# KAKUTE_mini.net
KiCad netlist of a schematic drawn in EasyEDA Pro
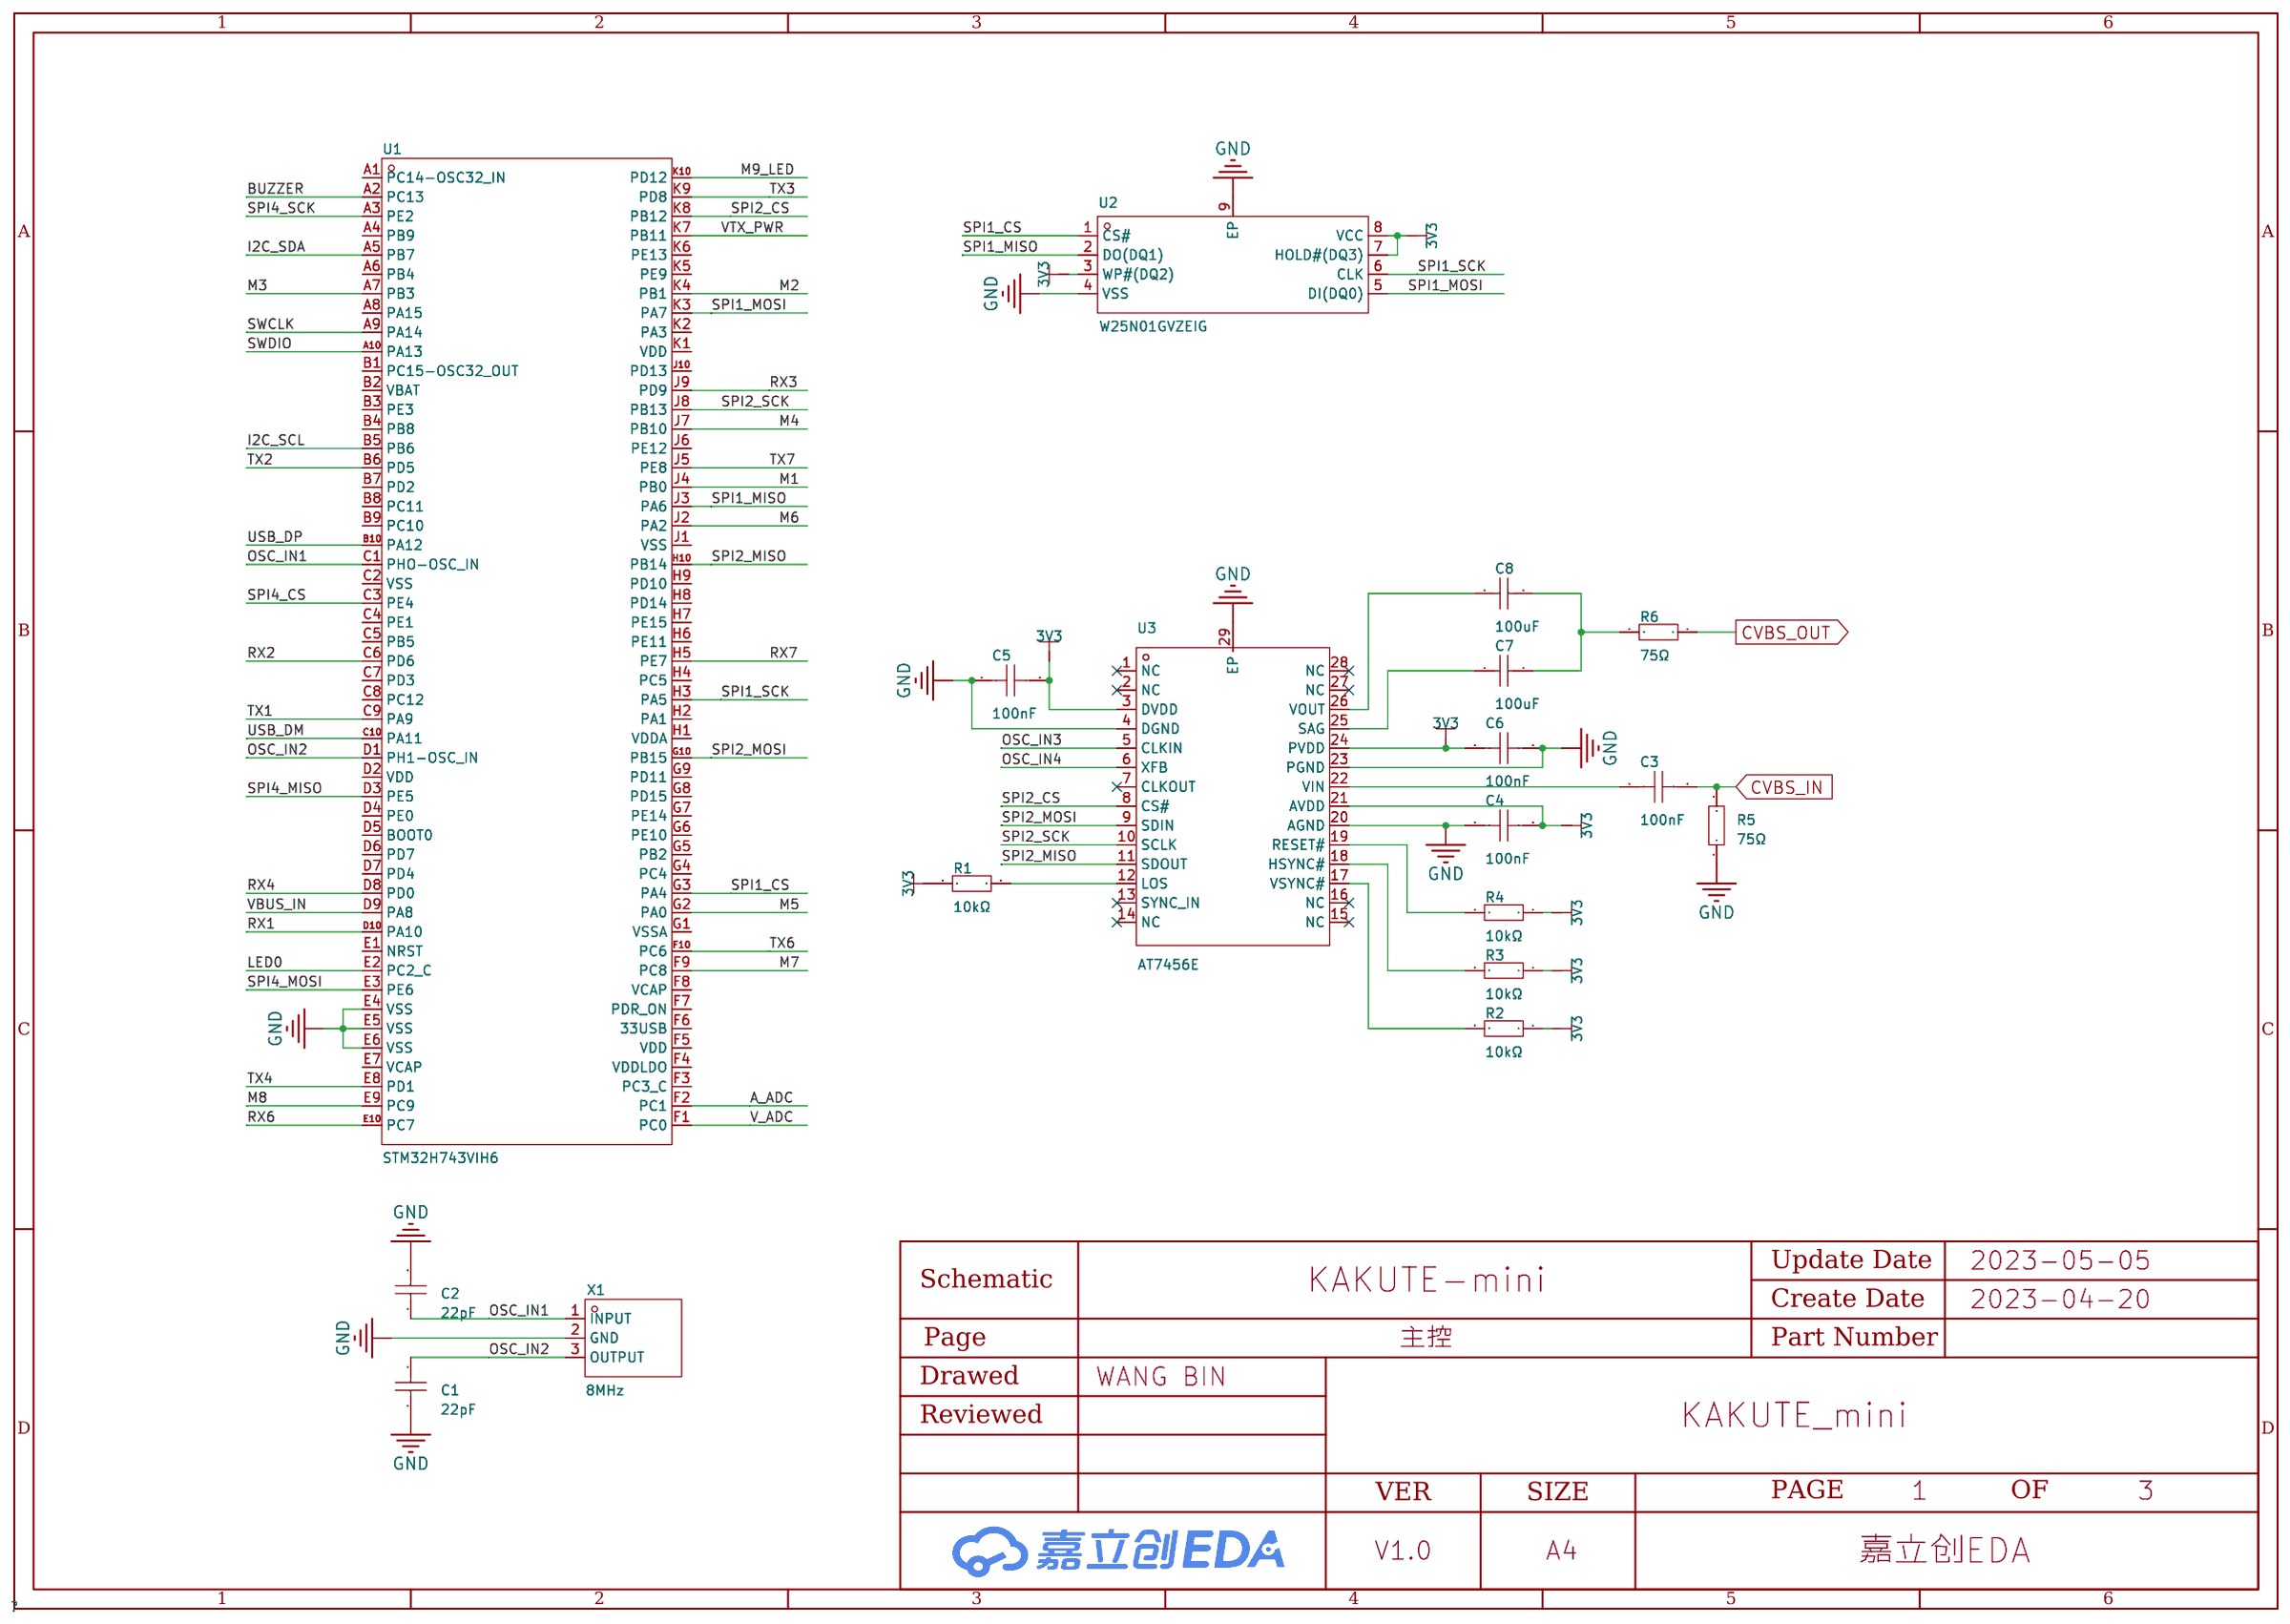
[diagram p0: 主控]
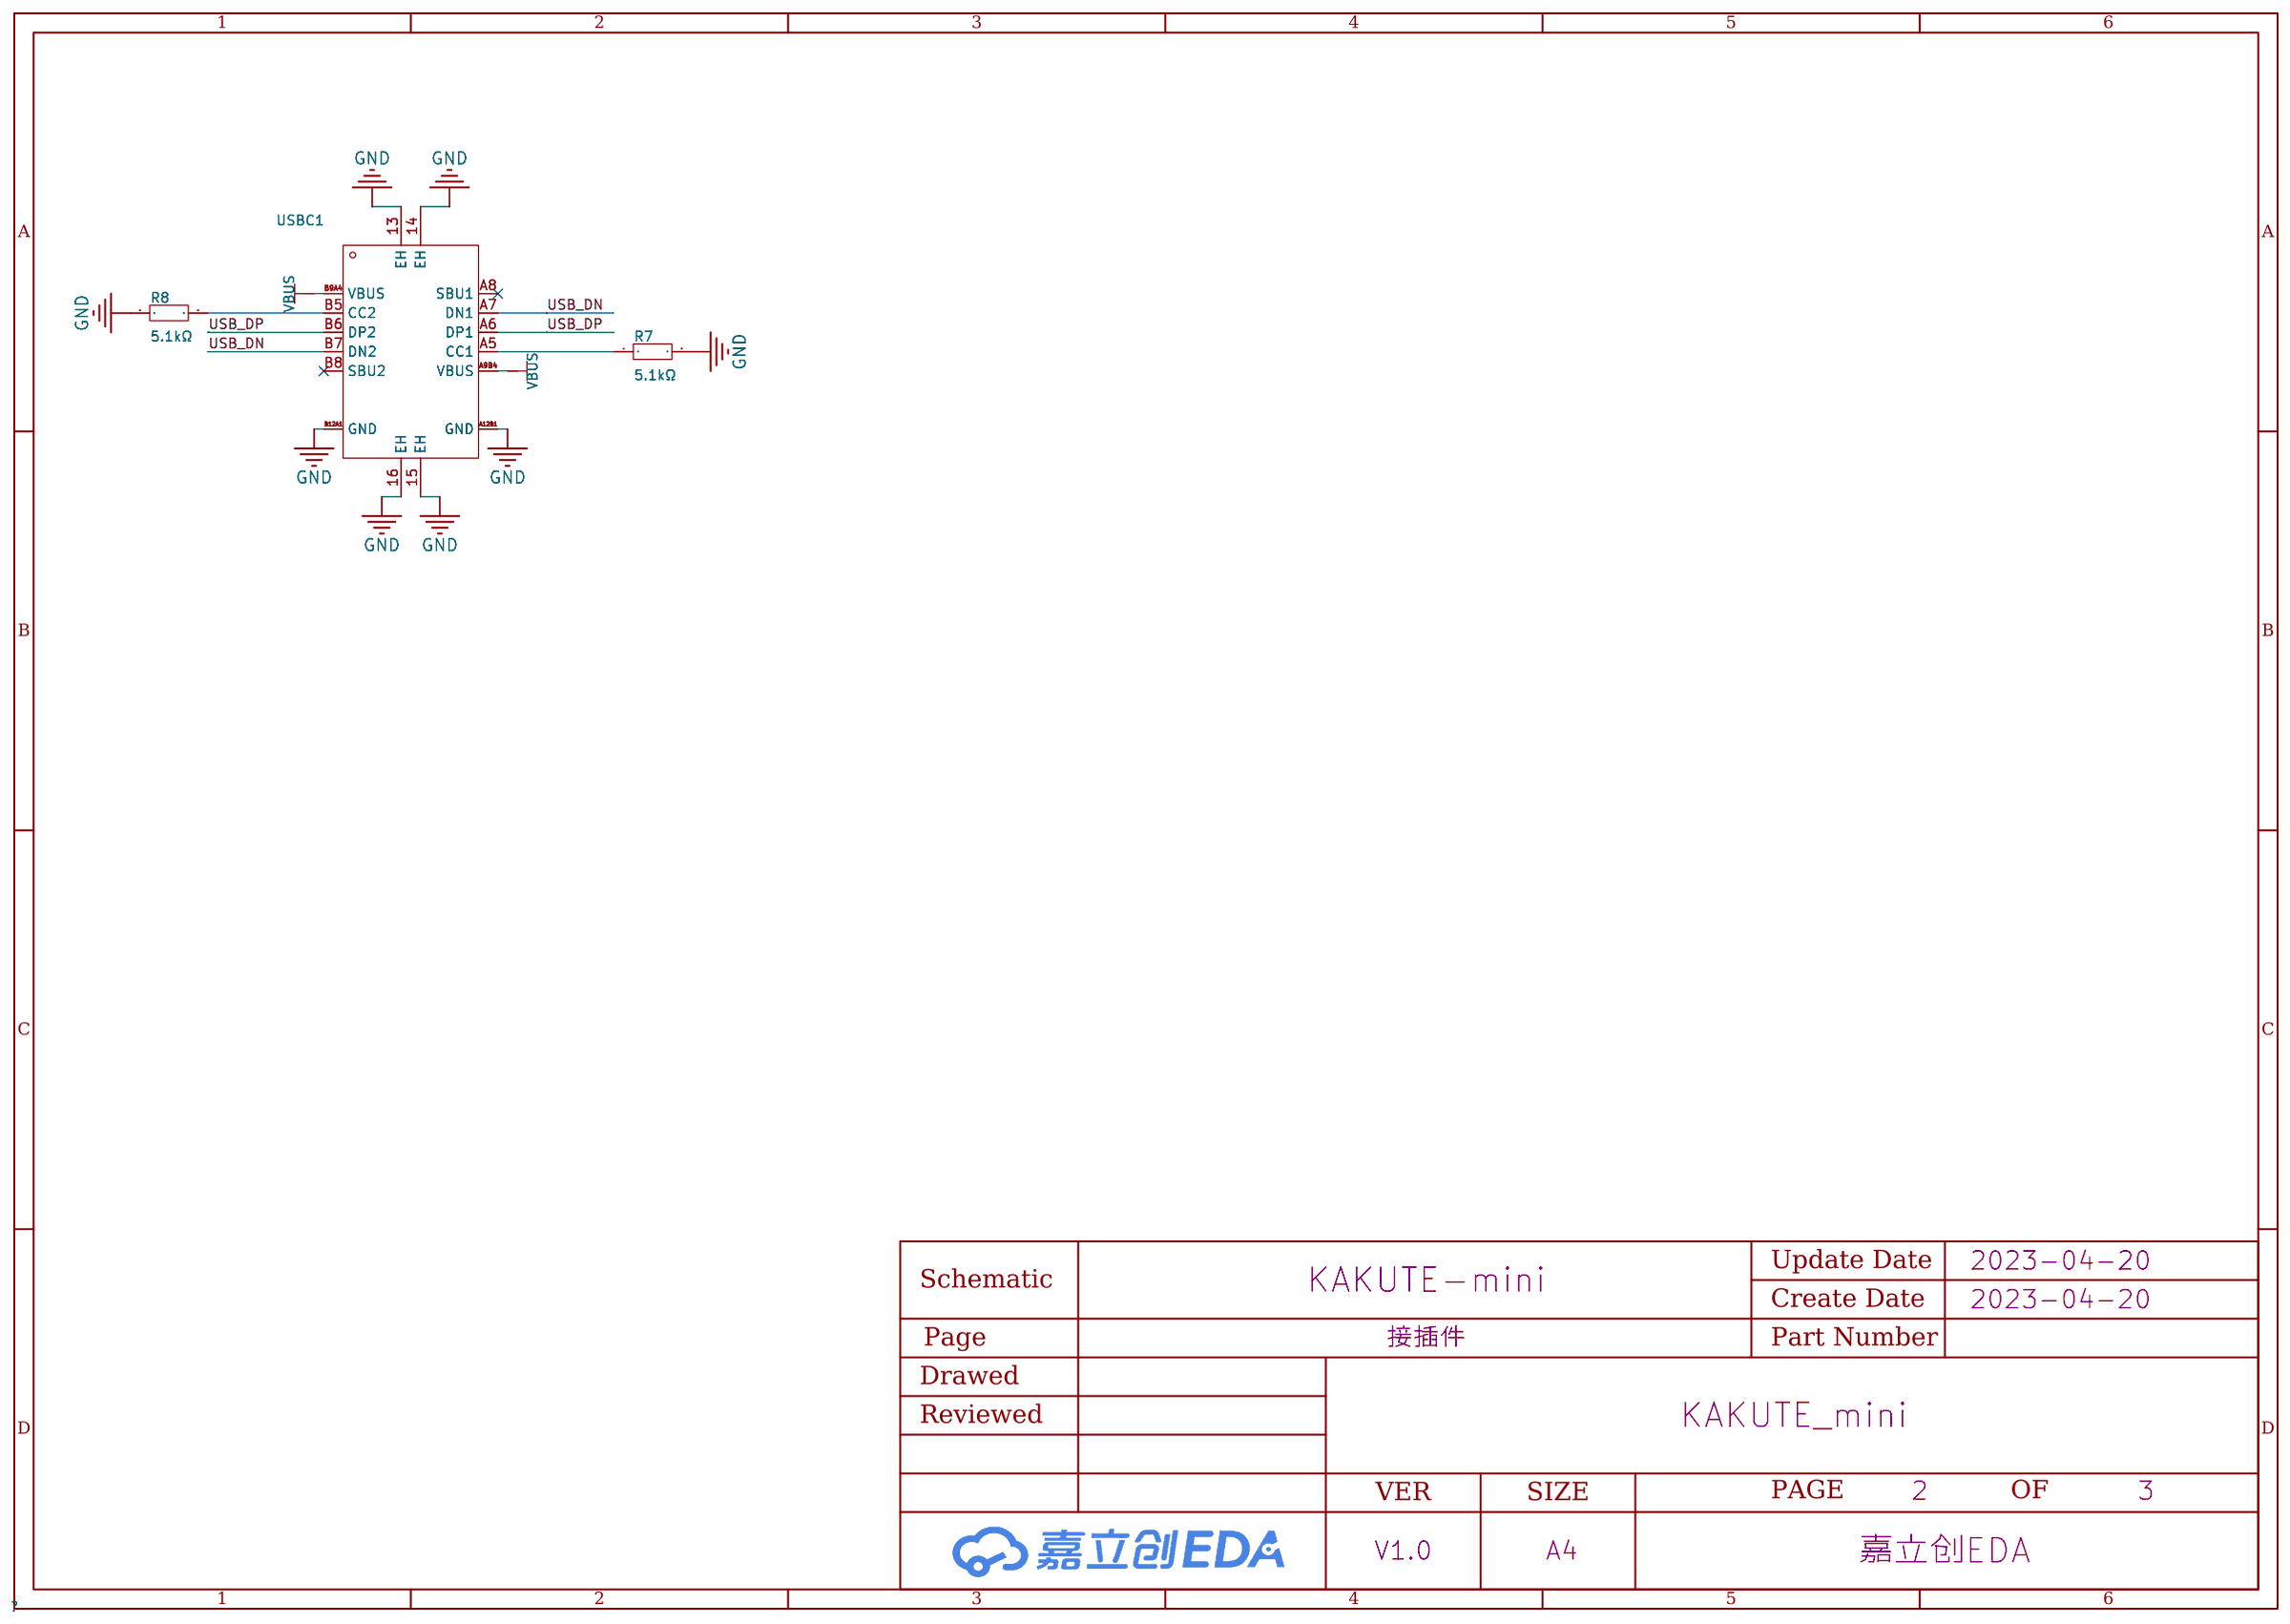
[diagram p1: 接插件]
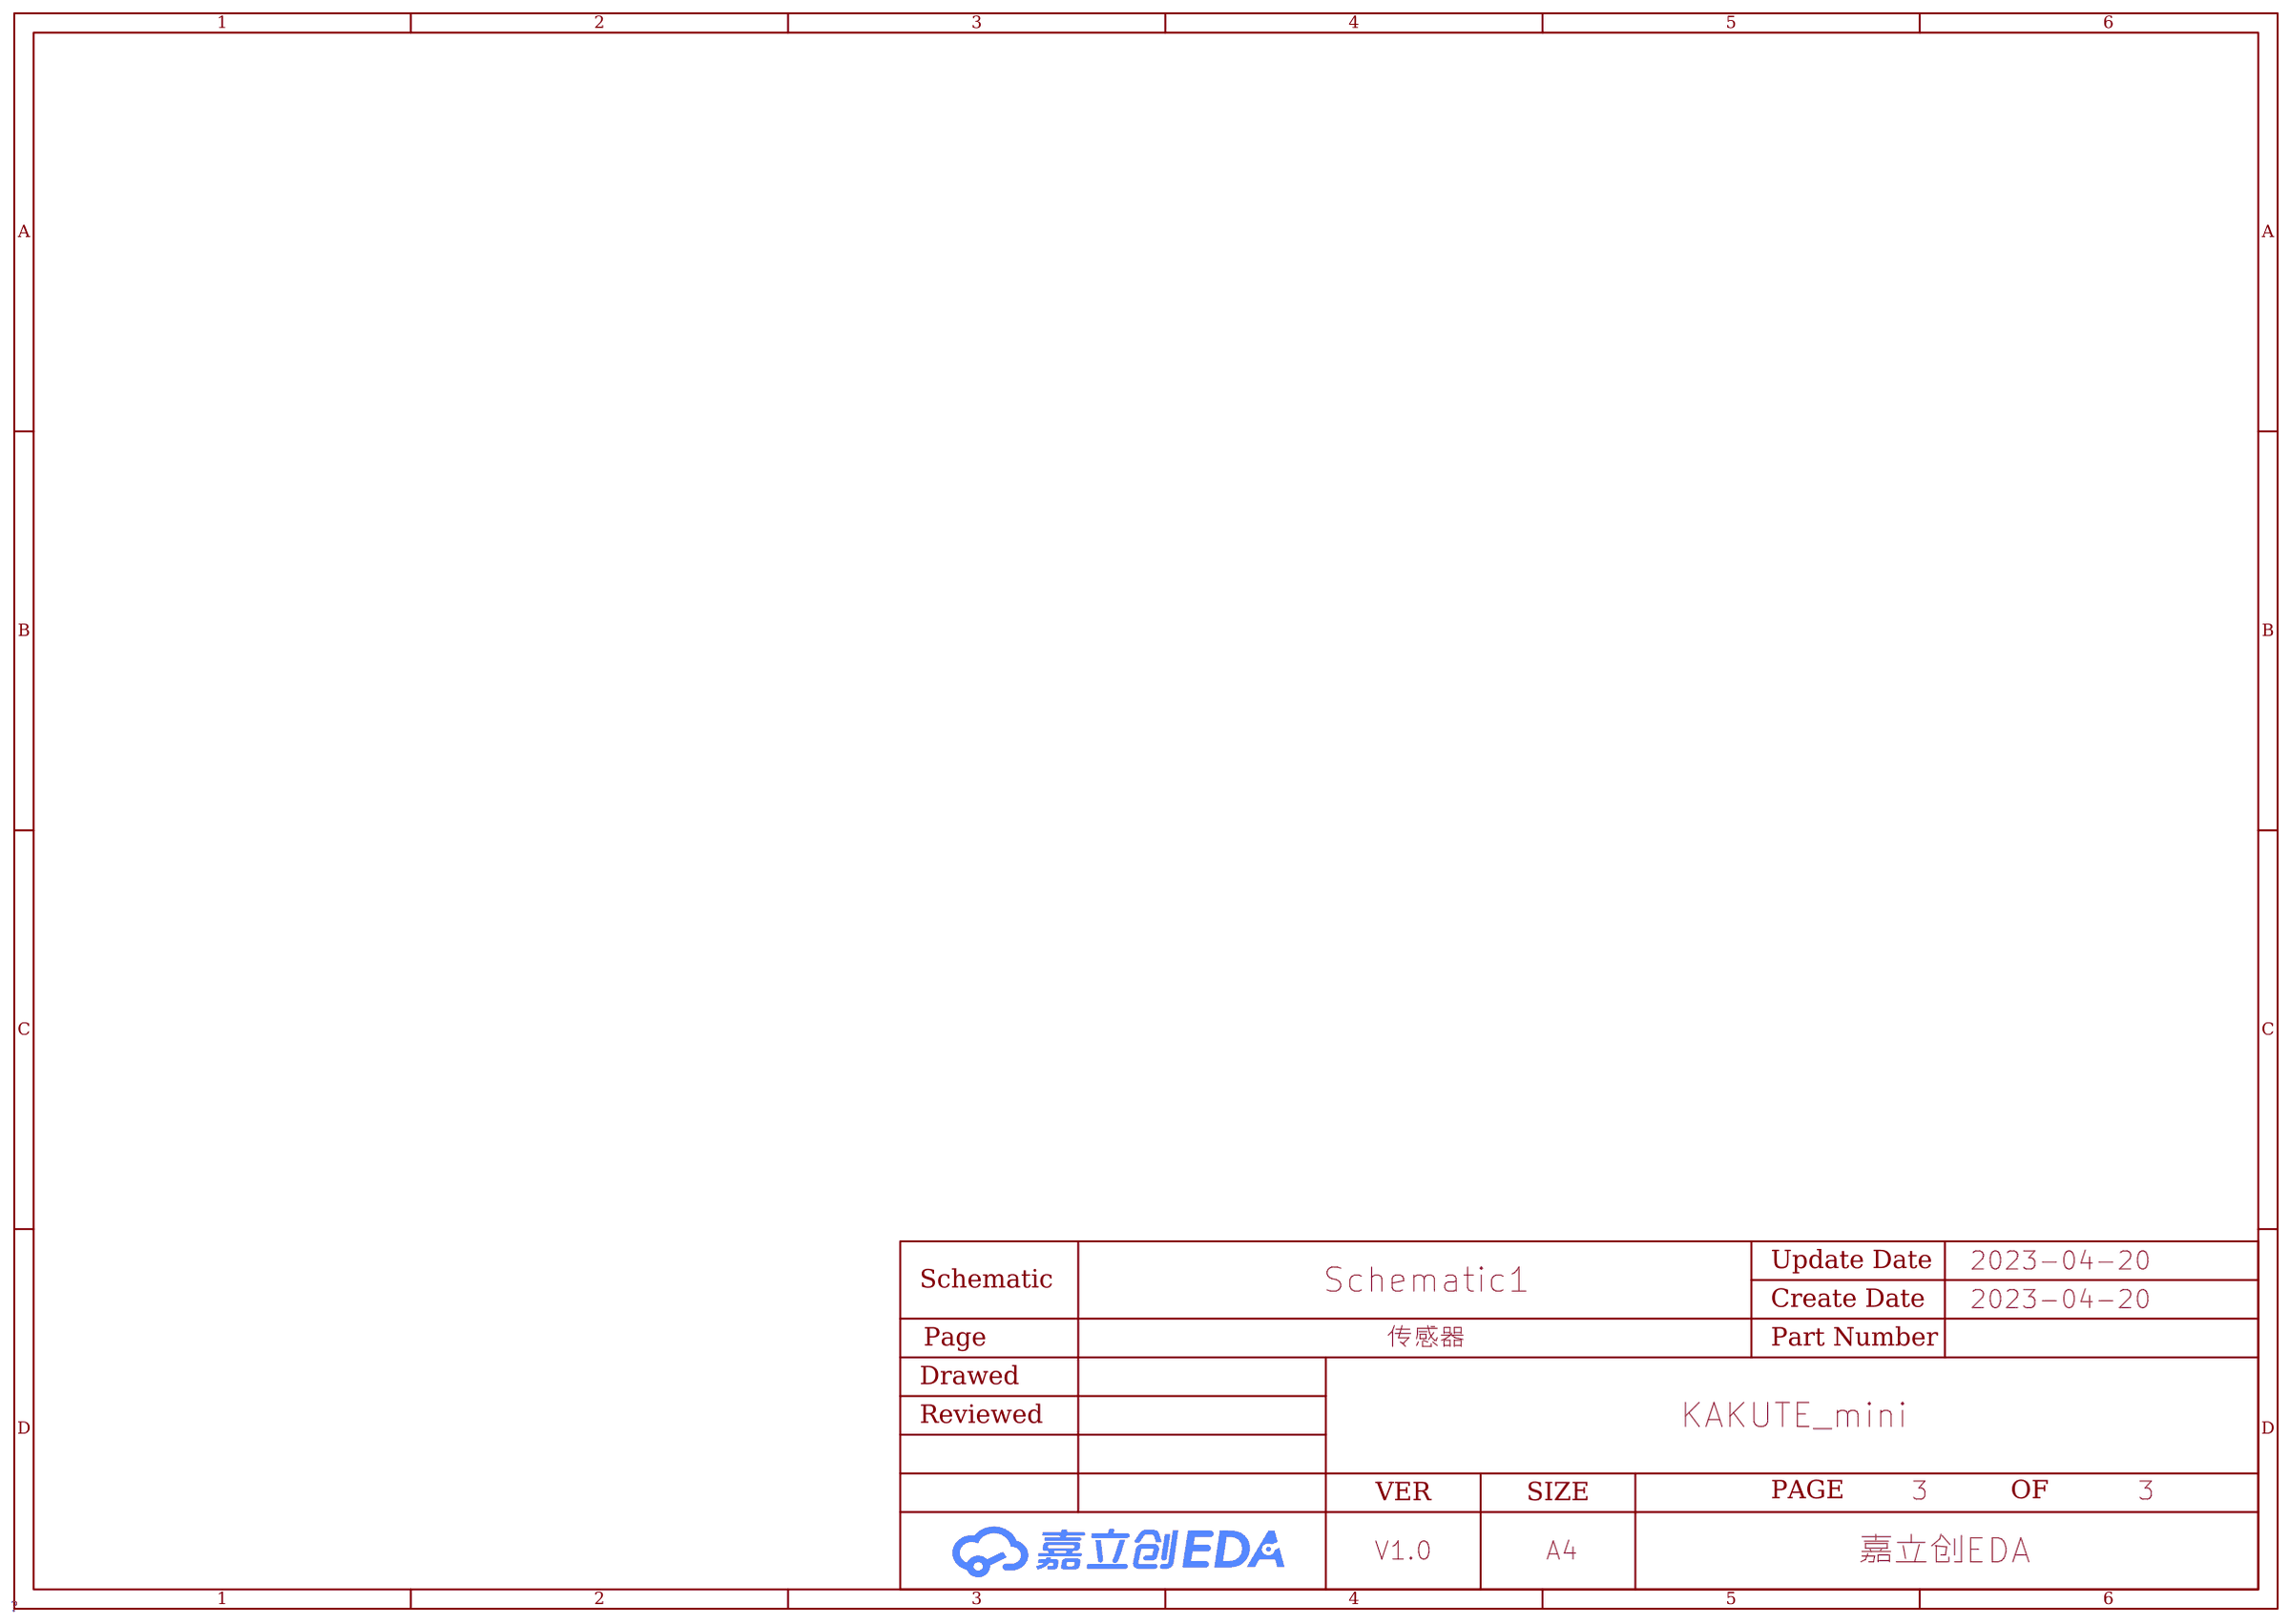
[diagram p2: 传感器]

(export (version "E")
  (design (tool "Eeschema 10.0.6"))
  (components
    (comp (ref "C1")
      (value "22pF")
      (footprint "easyedapro:C0402")
      (description "容值:22pF;精度:±5%;额定电压:50V;材质(温度系数):C0G;")
      (fields (field (name "Manufacturer Part") "0402CG220J500NT") (field (name "Manufacturer") "FH(风华)"))
      (libsource (lib "easyedapro") (part "0402CG220J500NT"))
    )
    (comp (ref "C2")
      (value "22pF")
      (footprint "easyedapro:C0402")
      (description "容值:22pF;精度:±5%;额定电压:50V;材质(温度系数):C0G;")
      (fields (field (name "Manufacturer Part") "0402CG220J500NT") (field (name "Manufacturer") "FH(风华)"))
      (libsource (lib "easyedapro") (part "0402CG220J500NT"))
    )
    (comp (ref "C3")
      (value "100nF")
      (footprint "easyedapro:C0402")
      (description "容值:100nF;精度:±10%;额定电压:50V;材质(温度系数):X7R;")
      (fields
        (field (name "Manufacturer Part") "CL05B104KB54PNC")
        (field (name "Manufacturer") "SAMSUNG(三星)")
      )
      (libsource (lib "easyedapro") (part "CL05B104KB54PNC"))
    )
    (comp (ref "C4")
      (value "100nF")
      (footprint "easyedapro:C0402")
      (description "容值:100nF;精度:±10%;额定电压:50V;材质(温度系数):X7R;")
      (fields
        (field (name "Manufacturer Part") "CL05B104KB54PNC")
        (field (name "Manufacturer") "SAMSUNG(三星)")
      )
      (libsource (lib "easyedapro") (part "CL05B104KB54PNC"))
    )
    (comp (ref "C5")
      (value "100nF")
      (footprint "easyedapro:C0402")
      (description "容值:100nF;精度:±10%;额定电压:50V;材质(温度系数):X7R;")
      (fields
        (field (name "Manufacturer Part") "CL05B104KB54PNC")
        (field (name "Manufacturer") "SAMSUNG(三星)")
      )
      (libsource (lib "easyedapro") (part "CL05B104KB54PNC"))
    )
    (comp (ref "C6")
      (value "100nF")
      (footprint "easyedapro:C0402")
      (description "容值:100nF;精度:±10%;额定电压:50V;材质(温度系数):X7R;")
      (fields
        (field (name "Manufacturer Part") "CL05B104KB54PNC")
        (field (name "Manufacturer") "SAMSUNG(三星)")
      )
      (libsource (lib "easyedapro") (part "CL05B104KB54PNC"))
    )
    (comp (ref "C7")
      (value "100uF")
      (footprint "easyedapro:C0805")
      (description "容值:100uF;精度:±20%;额定电压:6.3V;材质(温度系数):X5R;")
      (fields
        (field (name "Manufacturer Part") "GRM21BR60J107ME15L")
        (field (name "Manufacturer") "muRata(村田)")
      )
      (libsource (lib "easyedapro") (part "GRM21BR60J107ME15L"))
    )
    (comp (ref "C8")
      (value "100uF")
      (footprint "easyedapro:C0805")
      (description "容值:100uF;精度:±20%;额定电压:6.3V;材质(温度系数):X5R;")
      (fields
        (field (name "Manufacturer Part") "GRM21BR60J107ME15L")
        (field (name "Manufacturer") "muRata(村田)")
      )
      (libsource (lib "easyedapro") (part "GRM21BR60J107ME15L"))
    )
    (comp (ref "R1")
      (value "10kΩ")
      (footprint "easyedapro:R0402")
      (description "电阻类型:厚膜电阻;阻值:10kΩ;精度:±1%;功率:62.5mW;")
      (fields
        (field (name "Manufacturer Part") "0402WGF1002TCE")
        (field (name "Manufacturer") "UNI-ROYAL(厚声)")
      )
      (libsource (lib "easyedapro") (part "0402WGF1002TCE"))
    )
    (comp (ref "R2")
      (value "10kΩ")
      (footprint "easyedapro:R0402")
      (description "电阻类型:厚膜电阻;阻值:10kΩ;精度:±1%;功率:62.5mW;")
      (fields
        (field (name "Manufacturer Part") "0402WGF1002TCE")
        (field (name "Manufacturer") "UNI-ROYAL(厚声)")
      )
      (libsource (lib "easyedapro") (part "0402WGF1002TCE"))
    )
    (comp (ref "R3")
      (value "10kΩ")
      (footprint "easyedapro:R0402")
      (description "电阻类型:厚膜电阻;阻值:10kΩ;精度:±1%;功率:62.5mW;")
      (fields
        (field (name "Manufacturer Part") "0402WGF1002TCE")
        (field (name "Manufacturer") "UNI-ROYAL(厚声)")
      )
      (libsource (lib "easyedapro") (part "0402WGF1002TCE"))
    )
    (comp (ref "R4")
      (value "10kΩ")
      (footprint "easyedapro:R0402")
      (description "电阻类型:厚膜电阻;阻值:10kΩ;精度:±1%;功率:62.5mW;")
      (fields
        (field (name "Manufacturer Part") "0402WGF1002TCE")
        (field (name "Manufacturer") "UNI-ROYAL(厚声)")
      )
      (libsource (lib "easyedapro") (part "0402WGF1002TCE"))
    )
    (comp (ref "R5")
      (value "75Ω")
      (footprint "easyedapro:R0402")
      (description "电阻类型:厚膜电阻;阻值:75Ω;精度:±1%;功率:62.5mW;")
      (fields
        (field (name "Manufacturer Part") "0402WGF750JTCE")
        (field (name "Manufacturer") "UNI-ROYAL(厚声)")
      )
      (libsource (lib "easyedapro") (part "0402WGF750JTCE"))
    )
    (comp (ref "R6")
      (value "75Ω")
      (footprint "easyedapro:R0402")
      (description "电阻类型:厚膜电阻;阻值:75Ω;精度:±1%;功率:62.5mW;")
      (fields
        (field (name "Manufacturer Part") "0402WGF750JTCE")
        (field (name "Manufacturer") "UNI-ROYAL(厚声)")
      )
      (libsource (lib "easyedapro") (part "0402WGF750JTCE"))
    )
    (comp (ref "U1")
      (value "STM32H743VIH6")
      (footprint "easyedapro:BGA-100_L8.0-W8.0-P0.80-R10-C10-BL")
      (description "32位Arm Cortex -M7 480MHz mcu,高达2MB的Flash,高达1MB的RAM,46com和模拟接口")
      (fields (field (name "Manufacturer") "ST(意法半导体)"))
      (libsource (lib "easyedapro") (part "STM32H743VIH6"))
    )
    (comp (ref "U2")
      (value "W25N01GVZEIG")
      (footprint "easyedapro:WSON-8_L8.0-W6.10-P1.27-BL-EP")
      (description "存储器类型:-;存储器构架(格式):-;技术:-;存储器容量:-;时钟频率:-;存储器接口类型:-;")
      (fields (field (name "Manufacturer") "WINBOND(华邦)"))
      (libsource (lib "easyedapro") (part "W25N01GVZEIG_C907680"))
    )
    (comp (ref "U3")
      (value "AT7456E")
      (footprint "easyedapro:TSSOP-28_L9.7-W4.4-P0.65-LS6.4-BL-EP-2")
      (description "视频字符叠加芯片，跟MAX7456-pin-pin")
      (fields (field (name "Manufacturer") "杭州中科微"))
      (libsource (lib "easyedapro") (part "AT7456E"))
    )
    (comp (ref "X1")
      (value "8MHz")
      (footprint "easyedapro:OSC-SMD_3P-L3.2-W1.3-P1.20-L")
      (description "频率:8MHz;频率公差:±0.07%;频率稳定度:-;")
      (fields
        (field (name "Manufacturer Part") "CSTNE8M00GH5L000R0")
        (field (name "Manufacturer") "muRata(村田)")
      )
      (libsource (lib "easyedapro") (part "CSTNE8M00GH5L000R0"))
    )
    (comp (ref "R7")
      (value "5.1kΩ")
      (footprint "easyedapro:R0402")
      (description "电阻类型:厚膜电阻;阻值:5.1kΩ;精度:±1%;功率:62.5mW;")
      (fields
        (field (name "Manufacturer Part") "0402WGF5101TCE")
        (field (name "Manufacturer") "UNI-ROYAL(厚声)")
      )
      (libsource (lib "easyedapro") (part "0402WGF5101TCE"))
    )
    (comp (ref "R8")
      (value "5.1kΩ")
      (footprint "easyedapro:R0402")
      (description "电阻类型:厚膜电阻;阻值:5.1kΩ;精度:±1%;功率:62.5mW;")
      (fields
        (field (name "Manufacturer Part") "0402WGF5101TCE")
        (field (name "Manufacturer") "UNI-ROYAL(厚声)")
      )
      (libsource (lib "easyedapro") (part "0402WGF5101TCE"))
    )
    (comp (ref "USBC1")
      (value "918-418K2024S40000")
      (footprint "easyedapro:USB-C-SMD_TYPE-C-USB-4")
      (description "连接器类型:Type-C;标准:-;公母:母座;触点数量:16;端口数量:1;")
      (fields (field (name "Manufacturer") "精拓金"))
      (libsource (lib "easyedapro") (part "TYPE-C 3.1 MT 16P_C168688"))
    )
  )
  (nets
    (net (code "1") (name "3V3") (class "Default")
      (node (ref "C4") (pin "2") (pinfunction "2_2") (pintype "input"))
      (node (ref "C5") (pin "2") (pinfunction "2_2") (pintype "input"))
      (node (ref "C6") (pin "1") (pinfunction "1_1") (pintype "input"))
      (node (ref "R1") (pin "1") (pinfunction "1_1") (pintype "input"))
      (node (ref "R2") (pin "1") (pinfunction "1_1") (pintype "input"))
      (node (ref "R3") (pin "1") (pinfunction "1_1") (pintype "input"))
      (node (ref "R4") (pin "1") (pinfunction "1_1") (pintype "input"))
      (node (ref "U2") (pin "3") (pinfunction "WP#(DQ2)_3") (pintype "input"))
      (node (ref "U2") (pin "7") (pinfunction "HOLD#(DQ3)_7") (pintype "input"))
      (node (ref "U2") (pin "8") (pinfunction "VCC_8") (pintype "input"))
      (node (ref "U3") (pin "21") (pinfunction "AVDD_21") (pintype "input"))
      (node (ref "U3") (pin "24") (pinfunction "PVDD_24") (pintype "input"))
      (node (ref "U3") (pin "3") (pinfunction "DVDD_3") (pintype "input"))
    )
    (net (code "2") (name "A_ADC") (class "Default")
      (node (ref "U1") (pin "F2") (pinfunction "PC1_F2") (pintype "input"))
    )
    (net (code "3") (name "BUZZER") (class "Default")
      (node (ref "U1") (pin "A2") (pinfunction "PC13_A2") (pintype "input"))
    )
    (net (code "4") (name "CVBS_IN") (class "Default")
      (node (ref "C3") (pin "2") (pinfunction "2_2") (pintype "input"))
      (node (ref "R5") (pin "2") (pinfunction "2_2") (pintype "input"))
    )
    (net (code "5") (name "CVBS_OUT") (class "Default")
      (node (ref "R6") (pin "1") (pinfunction "1_1") (pintype "input"))
    )
    (net (code "6") (name "GND") (class "Default")
      (node (ref "C1") (pin "2") (pinfunction "2_2") (pintype "input"))
      (node (ref "C2") (pin "2") (pinfunction "2_2") (pintype "input"))
      (node (ref "C4") (pin "1") (pinfunction "1_1") (pintype "input"))
      (node (ref "C5") (pin "1") (pinfunction "1_1") (pintype "input"))
      (node (ref "C6") (pin "2") (pinfunction "2_2") (pintype "input"))
      (node (ref "R5") (pin "1") (pinfunction "1_1") (pintype "input"))
      (node (ref "R7") (pin "2") (pinfunction "2_2") (pintype "input"))
      (node (ref "R8") (pin "1") (pinfunction "1_1") (pintype "input"))
      (node (ref "U1") (pin "E4") (pinfunction "VSS_E4") (pintype "input"))
      (node (ref "U1") (pin "E5") (pinfunction "VSS_E5") (pintype "input"))
      (node (ref "U1") (pin "E6") (pinfunction "VSS_E6") (pintype "input"))
      (node (ref "U2") (pin "4") (pinfunction "VSS_4") (pintype "input"))
      (node (ref "U2") (pin "9") (pinfunction "EP_9") (pintype "input"))
      (node (ref "U3") (pin "20") (pinfunction "AGND_20") (pintype "input"))
      (node (ref "U3") (pin "23") (pinfunction "PGND_23") (pintype "input"))
      (node (ref "U3") (pin "29") (pinfunction "EP_29") (pintype "input"))
      (node (ref "U3") (pin "4") (pinfunction "DGND_4") (pintype "input"))
      (node (ref "USBC1") (pin "13") (pinfunction "EH_13") (pintype "input"))
      (node (ref "USBC1") (pin "14") (pinfunction "EH_14") (pintype "input"))
      (node (ref "USBC1") (pin "15") (pinfunction "EH_15") (pintype "input"))
      (node (ref "USBC1") (pin "16") (pinfunction "EH_16") (pintype "input"))
      (node (ref "USBC1") (pin "A12B1") (pinfunction "GND_A12B1") (pintype "input"))
      (node (ref "USBC1") (pin "B12A1") (pinfunction "GND_B12A1") (pintype "input"))
      (node (ref "X1") (pin "2") (pinfunction "GND_2") (pintype "input"))
    )
    (net (code "7") (name "I2C_SCL") (class "Default")
      (node (ref "U1") (pin "B5") (pinfunction "PB6_B5") (pintype "input"))
    )
    (net (code "8") (name "I2C_SDA") (class "Default")
      (node (ref "U1") (pin "A5") (pinfunction "PB7_A5") (pintype "input"))
    )
    (net (code "9") (name "LED0") (class "Default")
      (node (ref "U1") (pin "E2") (pinfunction "PC2_C_E2") (pintype "input"))
    )
    (net (code "10") (name "M1") (class "Default")
      (node (ref "U1") (pin "J4") (pinfunction "PB0_J4") (pintype "input"))
    )
    (net (code "11") (name "M2") (class "Default")
      (node (ref "U1") (pin "K4") (pinfunction "PB1_K4") (pintype "input"))
    )
    (net (code "12") (name "M3") (class "Default")
      (node (ref "U1") (pin "A7") (pinfunction "PB3_A7") (pintype "input"))
    )
    (net (code "13") (name "M4") (class "Default")
      (node (ref "U1") (pin "J7") (pinfunction "PB10_J7") (pintype "input"))
    )
    (net (code "14") (name "M5") (class "Default")
      (node (ref "U1") (pin "G2") (pinfunction "PA0_G2") (pintype "input"))
    )
    (net (code "15") (name "M6") (class "Default")
      (node (ref "U1") (pin "J2") (pinfunction "PA2_J2") (pintype "input"))
    )
    (net (code "16") (name "M7") (class "Default")
      (node (ref "U1") (pin "F9") (pinfunction "PC8_F9") (pintype "input"))
    )
    (net (code "17") (name "M8") (class "Default")
      (node (ref "U1") (pin "E9") (pinfunction "PC9_E9") (pintype "input"))
    )
    (net (code "18") (name "M9_LED") (class "Default")
      (node (ref "U1") (pin "K10") (pinfunction "PD12_K10") (pintype "input"))
    )
    (net (code "19") (name "Net-(C7-Pad2)") (class "Default")
      (node (ref "C7") (pin "2") (pinfunction "2_2") (pintype "input"))
      (node (ref "C8") (pin "2") (pinfunction "2_2") (pintype "input"))
      (node (ref "R6") (pin "2") (pinfunction "2_2") (pintype "input"))
    )
    (net (code "20") (name "Net-(U3-HSYNC#)") (class "Default")
      (node (ref "R3") (pin "2") (pinfunction "2_2") (pintype "input"))
      (node (ref "U3") (pin "18") (pinfunction "HSYNC#_18") (pintype "input"))
    )
    (net (code "21") (name "Net-(U3-LOS)") (class "Default")
      (node (ref "R1") (pin "2") (pinfunction "2_2") (pintype "input"))
      (node (ref "U3") (pin "12") (pinfunction "LOS_12") (pintype "input"))
    )
    (net (code "22") (name "Net-(U3-RESET#)") (class "Default")
      (node (ref "R4") (pin "2") (pinfunction "2_2") (pintype "input"))
      (node (ref "U3") (pin "19") (pinfunction "RESET#_19") (pintype "input"))
    )
    (net (code "23") (name "Net-(U3-SAG)") (class "Default")
      (node (ref "C7") (pin "1") (pinfunction "1_1") (pintype "input"))
      (node (ref "U3") (pin "25") (pinfunction "SAG_25") (pintype "input"))
    )
    (net (code "24") (name "Net-(U3-VIN)") (class "Default")
      (node (ref "C3") (pin "1") (pinfunction "1_1") (pintype "input"))
      (node (ref "U3") (pin "22") (pinfunction "VIN_22") (pintype "input"))
    )
    (net (code "25") (name "Net-(U3-VOUT)") (class "Default")
      (node (ref "C8") (pin "1") (pinfunction "1_1") (pintype "input"))
      (node (ref "U3") (pin "26") (pinfunction "VOUT_26") (pintype "input"))
    )
    (net (code "26") (name "Net-(U3-VSYNC#)") (class "Default")
      (node (ref "R2") (pin "2") (pinfunction "2_2") (pintype "input"))
      (node (ref "U3") (pin "17") (pinfunction "VSYNC#_17") (pintype "input"))
    )
    (net (code "27") (name "Net-(USBC1-CC1)") (class "Default")
      (node (ref "R7") (pin "1") (pinfunction "1_1") (pintype "input"))
      (node (ref "USBC1") (pin "A5") (pinfunction "CC1_A5") (pintype "input"))
    )
    (net (code "28") (name "Net-(USBC1-CC2)") (class "Default")
      (node (ref "R8") (pin "2") (pinfunction "2_2") (pintype "input"))
      (node (ref "USBC1") (pin "B5") (pinfunction "CC2_B5") (pintype "input"))
    )
    (net (code "29") (name "OSC_IN1") (class "Default")
      (node (ref "C2") (pin "1") (pinfunction "1_1") (pintype "input"))
      (node (ref "U1") (pin "C1") (pinfunction "PHO-OSC_IN_C1") (pintype "input"))
      (node (ref "X1") (pin "1") (pinfunction "INPUT_1") (pintype "input"))
    )
    (net (code "30") (name "OSC_IN2") (class "Default")
      (node (ref "C1") (pin "1") (pinfunction "1_1") (pintype "input"))
      (node (ref "U1") (pin "D1") (pinfunction "PH1-OSC_IN_D1") (pintype "input"))
      (node (ref "X1") (pin "3") (pinfunction "OUTPUT_3") (pintype "input"))
    )
    (net (code "31") (name "OSC_IN3") (class "Default")
      (node (ref "U3") (pin "5") (pinfunction "CLKIN_5") (pintype "input"))
    )
    (net (code "32") (name "OSC_IN4") (class "Default")
      (node (ref "U3") (pin "6") (pinfunction "XFB_6") (pintype "input"))
    )
    (net (code "33") (name "RX1") (class "Default")
      (node (ref "U1") (pin "D10") (pinfunction "PA10_D10") (pintype "input"))
    )
    (net (code "34") (name "RX2") (class "Default")
      (node (ref "U1") (pin "C6") (pinfunction "PD6_C6") (pintype "input"))
    )
    (net (code "35") (name "RX3") (class "Default")
      (node (ref "U1") (pin "J9") (pinfunction "PD9_J9") (pintype "input"))
    )
    (net (code "36") (name "RX4") (class "Default")
      (node (ref "U1") (pin "D8") (pinfunction "PD0_D8") (pintype "input"))
    )
    (net (code "37") (name "RX6") (class "Default")
      (node (ref "U1") (pin "E10") (pinfunction "PC7_E10") (pintype "input"))
    )
    (net (code "38") (name "RX7") (class "Default")
      (node (ref "U1") (pin "H5") (pinfunction "PE7_H5") (pintype "input"))
    )
    (net (code "39") (name "SPI1_CS") (class "Default")
      (node (ref "U1") (pin "G3") (pinfunction "PA4_G3") (pintype "input"))
      (node (ref "U2") (pin "1") (pinfunction "CS#_1") (pintype "input"))
    )
    (net (code "40") (name "SPI1_MISO") (class "Default")
      (node (ref "U1") (pin "J3") (pinfunction "PA6_J3") (pintype "input"))
      (node (ref "U2") (pin "2") (pinfunction "DO(DQ1)_2") (pintype "input"))
    )
    (net (code "41") (name "SPI1_MOSI") (class "Default")
      (node (ref "U1") (pin "K3") (pinfunction "PA7_K3") (pintype "input"))
      (node (ref "U2") (pin "5") (pinfunction "DI(DQ0)_5") (pintype "input"))
    )
    (net (code "42") (name "SPI1_SCK") (class "Default")
      (node (ref "U1") (pin "H3") (pinfunction "PA5_H3") (pintype "input"))
      (node (ref "U2") (pin "6") (pinfunction "CLK_6") (pintype "input"))
    )
    (net (code "43") (name "SPI2_CS") (class "Default")
      (node (ref "U1") (pin "K8") (pinfunction "PB12_K8") (pintype "input"))
      (node (ref "U3") (pin "8") (pinfunction "CS#_8") (pintype "input"))
    )
    (net (code "44") (name "SPI2_MISO") (class "Default")
      (node (ref "U1") (pin "H10") (pinfunction "PB14_H10") (pintype "input"))
      (node (ref "U3") (pin "11") (pinfunction "SDOUT_11") (pintype "input"))
    )
    (net (code "45") (name "SPI2_MOSI") (class "Default")
      (node (ref "U1") (pin "G10") (pinfunction "PB15_G10") (pintype "input"))
      (node (ref "U3") (pin "9") (pinfunction "SDIN_9") (pintype "input"))
    )
    (net (code "46") (name "SPI2_SCK") (class "Default")
      (node (ref "U1") (pin "J8") (pinfunction "PB13_J8") (pintype "input"))
      (node (ref "U3") (pin "10") (pinfunction "SCLK_10") (pintype "input"))
    )
    (net (code "47") (name "SPI4_CS") (class "Default")
      (node (ref "U1") (pin "C3") (pinfunction "PE4_C3") (pintype "input"))
    )
    (net (code "48") (name "SPI4_MISO") (class "Default")
      (node (ref "U1") (pin "D3") (pinfunction "PE5_D3") (pintype "input"))
    )
    (net (code "49") (name "SPI4_MOSI") (class "Default")
      (node (ref "U1") (pin "E3") (pinfunction "PE6_E3") (pintype "input"))
    )
    (net (code "50") (name "SPI4_SCK") (class "Default")
      (node (ref "U1") (pin "A3") (pinfunction "PE2_A3") (pintype "input"))
    )
    (net (code "51") (name "SWCLK") (class "Default")
      (node (ref "U1") (pin "A9") (pinfunction "PA14_A9") (pintype "input"))
    )
    (net (code "52") (name "SWDIO") (class "Default")
      (node (ref "U1") (pin "A10") (pinfunction "PA13_A10") (pintype "input"))
    )
    (net (code "53") (name "TX1") (class "Default")
      (node (ref "U1") (pin "C9") (pinfunction "PA9_C9") (pintype "input"))
    )
    (net (code "54") (name "TX2") (class "Default")
      (node (ref "U1") (pin "B6") (pinfunction "PD5_B6") (pintype "input"))
    )
    (net (code "55") (name "TX3") (class "Default")
      (node (ref "U1") (pin "K9") (pinfunction "PD8_K9") (pintype "input"))
    )
    (net (code "56") (name "TX4") (class "Default")
      (node (ref "U1") (pin "E8") (pinfunction "PD1_E8") (pintype "input"))
    )
    (net (code "57") (name "TX6") (class "Default")
      (node (ref "U1") (pin "F10") (pinfunction "PC6_F10") (pintype "input"))
    )
    (net (code "58") (name "TX7") (class "Default")
      (node (ref "U1") (pin "J5") (pinfunction "PE8_J5") (pintype "input"))
    )
    (net (code "59") (name "USB_DM") (class "Default")
      (node (ref "U1") (pin "C10") (pinfunction "PA11_C10") (pintype "input"))
    )
    (net (code "60") (name "USB_DN") (class "Default")
      (node (ref "USBC1") (pin "A7") (pinfunction "DN1_A7") (pintype "input"))
      (node (ref "USBC1") (pin "B7") (pinfunction "DN2_B7") (pintype "input"))
    )
    (net (code "61") (name "USB_DP") (class "Default")
      (node (ref "U1") (pin "B10") (pinfunction "PA12_B10") (pintype "input"))
      (node (ref "USBC1") (pin "A6") (pinfunction "DP1_A6") (pintype "input"))
      (node (ref "USBC1") (pin "B6") (pinfunction "DP2_B6") (pintype "input"))
    )
    (net (code "62") (name "VBUS") (class "Default")
      (node (ref "USBC1") (pin "A9B4") (pinfunction "VBUS_A9B4") (pintype "input"))
      (node (ref "USBC1") (pin "B9A4") (pinfunction "VBUS_B9A4") (pintype "input"))
    )
    (net (code "63") (name "VBUS_IN") (class "Default")
      (node (ref "U1") (pin "D9") (pinfunction "PA8_D9") (pintype "input"))
    )
    (net (code "64") (name "VTX_PWR") (class "Default")
      (node (ref "U1") (pin "K7") (pinfunction "PB11_K7") (pintype "input"))
    )
    (net (code "65") (name "V_ADC") (class "Default")
      (node (ref "U1") (pin "F1") (pinfunction "PC0_F1") (pintype "input"))
    )
    (net (code "66") (name "unconnected-(U1-33USB-PadF6)") (class "Default")
      (node (ref "U1") (pin "F6") (pinfunction "33USB_F6") (pintype "input"))
    )
    (net (code "67") (name "unconnected-(U1-BOOT0-PadD5)") (class "Default")
      (node (ref "U1") (pin "D5") (pinfunction "BOOT0_D5") (pintype "input"))
    )
    (net (code "68") (name "unconnected-(U1-NRST-PadE1)") (class "Default")
      (node (ref "U1") (pin "E1") (pinfunction "NRST_E1") (pintype "input"))
    )
    (net (code "69") (name "unconnected-(U1-PA1-PadH2)") (class "Default")
      (node (ref "U1") (pin "H2") (pinfunction "PA1_H2") (pintype "input"))
    )
    (net (code "70") (name "unconnected-(U1-PA3-PadK2)") (class "Default")
      (node (ref "U1") (pin "K2") (pinfunction "PA3_K2") (pintype "input"))
    )
    (net (code "71") (name "unconnected-(U1-PA15-PadA8)") (class "Default")
      (node (ref "U1") (pin "A8") (pinfunction "PA15_A8") (pintype "input"))
    )
    (net (code "72") (name "unconnected-(U1-PB2-PadG5)") (class "Default")
      (node (ref "U1") (pin "G5") (pinfunction "PB2_G5") (pintype "input"))
    )
    (net (code "73") (name "unconnected-(U1-PB4-PadA6)") (class "Default")
      (node (ref "U1") (pin "A6") (pinfunction "PB4_A6") (pintype "input"))
    )
    (net (code "74") (name "unconnected-(U1-PB5-PadC5)") (class "Default")
      (node (ref "U1") (pin "C5") (pinfunction "PB5_C5") (pintype "input"))
    )
    (net (code "75") (name "unconnected-(U1-PB8-PadB4)") (class "Default")
      (node (ref "U1") (pin "B4") (pinfunction "PB8_B4") (pintype "input"))
    )
    (net (code "76") (name "unconnected-(U1-PB9-PadA4)") (class "Default")
      (node (ref "U1") (pin "A4") (pinfunction "PB9_A4") (pintype "input"))
    )
    (net (code "77") (name "unconnected-(U1-PC3_C-PadF3)") (class "Default")
      (node (ref "U1") (pin "F3") (pinfunction "PC3_C_F3") (pintype "input"))
    )
    (net (code "78") (name "unconnected-(U1-PC4-PadG4)") (class "Default")
      (node (ref "U1") (pin "G4") (pinfunction "PC4_G4") (pintype "input"))
    )
    (net (code "79") (name "unconnected-(U1-PC5-PadH4)") (class "Default")
      (node (ref "U1") (pin "H4") (pinfunction "PC5_H4") (pintype "input"))
    )
    (net (code "80") (name "unconnected-(U1-PC10-PadB9)") (class "Default")
      (node (ref "U1") (pin "B9") (pinfunction "PC10_B9") (pintype "input"))
    )
    (net (code "81") (name "unconnected-(U1-PC11-PadB8)") (class "Default")
      (node (ref "U1") (pin "B8") (pinfunction "PC11_B8") (pintype "input"))
    )
    (net (code "82") (name "unconnected-(U1-PC12-PadC8)") (class "Default")
      (node (ref "U1") (pin "C8") (pinfunction "PC12_C8") (pintype "input"))
    )
    (net (code "83") (name "unconnected-(U1-PC14-OSC32_IN-PadA1)") (class "Default")
      (node (ref "U1") (pin "A1") (pinfunction "PC14-OSC32_IN_A1") (pintype "input"))
    )
    (net (code "84") (name "unconnected-(U1-PC15-OSC32_OUT-PadB1)") (class "Default")
      (node (ref "U1") (pin "B1") (pinfunction "PC15-OSC32_OUT_B1") (pintype "input"))
    )
    (net (code "85") (name "unconnected-(U1-PD2-PadB7)") (class "Default")
      (node (ref "U1") (pin "B7") (pinfunction "PD2_B7") (pintype "input"))
    )
    (net (code "86") (name "unconnected-(U1-PD3-PadC7)") (class "Default")
      (node (ref "U1") (pin "C7") (pinfunction "PD3_C7") (pintype "input"))
    )
    (net (code "87") (name "unconnected-(U1-PD4-PadD7)") (class "Default")
      (node (ref "U1") (pin "D7") (pinfunction "PD4_D7") (pintype "input"))
    )
    (net (code "88") (name "unconnected-(U1-PD7-PadD6)") (class "Default")
      (node (ref "U1") (pin "D6") (pinfunction "PD7_D6") (pintype "input"))
    )
    (net (code "89") (name "unconnected-(U1-PD10-PadH9)") (class "Default")
      (node (ref "U1") (pin "H9") (pinfunction "PD10_H9") (pintype "input"))
    )
    (net (code "90") (name "unconnected-(U1-PD11-PadG9)") (class "Default")
      (node (ref "U1") (pin "G9") (pinfunction "PD11_G9") (pintype "input"))
    )
    (net (code "91") (name "unconnected-(U1-PD13-PadJ10)") (class "Default")
      (node (ref "U1") (pin "J10") (pinfunction "PD13_J10") (pintype "input"))
    )
    (net (code "92") (name "unconnected-(U1-PD14-PadH8)") (class "Default")
      (node (ref "U1") (pin "H8") (pinfunction "PD14_H8") (pintype "input"))
    )
    (net (code "93") (name "unconnected-(U1-PD15-PadG8)") (class "Default")
      (node (ref "U1") (pin "G8") (pinfunction "PD15_G8") (pintype "input"))
    )
    (net (code "94") (name "unconnected-(U1-PDR_ON-PadF7)") (class "Default")
      (node (ref "U1") (pin "F7") (pinfunction "PDR_ON_F7") (pintype "input"))
    )
    (net (code "95") (name "unconnected-(U1-PE0-PadD4)") (class "Default")
      (node (ref "U1") (pin "D4") (pinfunction "PE0_D4") (pintype "input"))
    )
    (net (code "96") (name "unconnected-(U1-PE1-PadC4)") (class "Default")
      (node (ref "U1") (pin "C4") (pinfunction "PE1_C4") (pintype "input"))
    )
    (net (code "97") (name "unconnected-(U1-PE3-PadB3)") (class "Default")
      (node (ref "U1") (pin "B3") (pinfunction "PE3_B3") (pintype "input"))
    )
    (net (code "98") (name "unconnected-(U1-PE9-PadK5)") (class "Default")
      (node (ref "U1") (pin "K5") (pinfunction "PE9_K5") (pintype "input"))
    )
    (net (code "99") (name "unconnected-(U1-PE10-PadG6)") (class "Default")
      (node (ref "U1") (pin "G6") (pinfunction "PE10_G6") (pintype "input"))
    )
    (net (code "100") (name "unconnected-(U1-PE11-PadH6)") (class "Default")
      (node (ref "U1") (pin "H6") (pinfunction "PE11_H6") (pintype "input"))
    )
    (net (code "101") (name "unconnected-(U1-PE12-PadJ6)") (class "Default")
      (node (ref "U1") (pin "J6") (pinfunction "PE12_J6") (pintype "input"))
    )
    (net (code "102") (name "unconnected-(U1-PE13-PadK6)") (class "Default")
      (node (ref "U1") (pin "K6") (pinfunction "PE13_K6") (pintype "input"))
    )
    (net (code "103") (name "unconnected-(U1-PE14-PadG7)") (class "Default")
      (node (ref "U1") (pin "G7") (pinfunction "PE14_G7") (pintype "input"))
    )
    (net (code "104") (name "unconnected-(U1-PE15-PadH7)") (class "Default")
      (node (ref "U1") (pin "H7") (pinfunction "PE15_H7") (pintype "input"))
    )
    (net (code "105") (name "unconnected-(U1-VBAT-PadB2)") (class "Default")
      (node (ref "U1") (pin "B2") (pinfunction "VBAT_B2") (pintype "input"))
    )
    (net (code "106") (name "unconnected-(U1-VCAP-PadE7)") (class "Default")
      (node (ref "U1") (pin "E7") (pinfunction "VCAP_E7") (pintype "input"))
    )
    (net (code "107") (name "unconnected-(U1-VCAP-PadF8)") (class "Default")
      (node (ref "U1") (pin "F8") (pinfunction "VCAP_F8") (pintype "input"))
    )
    (net (code "108") (name "unconnected-(U1-VDD-PadD2)") (class "Default")
      (node (ref "U1") (pin "D2") (pinfunction "VDD_D2") (pintype "input"))
    )
    (net (code "109") (name "unconnected-(U1-VDD-PadF5)") (class "Default")
      (node (ref "U1") (pin "F5") (pinfunction "VDD_F5") (pintype "input"))
    )
    (net (code "110") (name "unconnected-(U1-VDD-PadK1)") (class "Default")
      (node (ref "U1") (pin "K1") (pinfunction "VDD_K1") (pintype "input"))
    )
    (net (code "111") (name "unconnected-(U1-VDDA-PadH1)") (class "Default")
      (node (ref "U1") (pin "H1") (pinfunction "VDDA_H1") (pintype "input"))
    )
    (net (code "112") (name "unconnected-(U1-VDDLDO-PadF4)") (class "Default")
      (node (ref "U1") (pin "F4") (pinfunction "VDDLDO_F4") (pintype "input"))
    )
    (net (code "113") (name "unconnected-(U1-VSS-PadC2)") (class "Default")
      (node (ref "U1") (pin "C2") (pinfunction "VSS_C2") (pintype "input"))
    )
    (net (code "114") (name "unconnected-(U1-VSS-PadJ1)") (class "Default")
      (node (ref "U1") (pin "J1") (pinfunction "VSS_J1") (pintype "input"))
    )
    (net (code "115") (name "unconnected-(U1-VSSA-PadG1)") (class "Default")
      (node (ref "U1") (pin "G1") (pinfunction "VSSA_G1") (pintype "input"))
    )
    (net (code "116") (name "unconnected-(U3-CLKOUT-Pad7)") (class "Default")
      (node (ref "U3") (pin "7") (pinfunction "CLKOUT_7") (pintype "input+no_connect"))
    )
    (net (code "117") (name "unconnected-(U3-NC-Pad1)") (class "Default")
      (node (ref "U3") (pin "1") (pinfunction "NC_1") (pintype "input+no_connect"))
    )
    (net (code "118") (name "unconnected-(U3-NC-Pad2)") (class "Default")
      (node (ref "U3") (pin "2") (pinfunction "NC_2") (pintype "input+no_connect"))
    )
    (net (code "119") (name "unconnected-(U3-NC-Pad14)") (class "Default")
      (node (ref "U3") (pin "14") (pinfunction "NC_14") (pintype "input+no_connect"))
    )
    (net (code "120") (name "unconnected-(U3-NC-Pad15)") (class "Default")
      (node (ref "U3") (pin "15") (pinfunction "NC_15") (pintype "input+no_connect"))
    )
    (net (code "121") (name "unconnected-(U3-NC-Pad16)") (class "Default")
      (node (ref "U3") (pin "16") (pinfunction "NC_16") (pintype "input+no_connect"))
    )
    (net (code "122") (name "unconnected-(U3-NC-Pad27)") (class "Default")
      (node (ref "U3") (pin "27") (pinfunction "NC_27") (pintype "input+no_connect"))
    )
    (net (code "123") (name "unconnected-(U3-NC-Pad28)") (class "Default")
      (node (ref "U3") (pin "28") (pinfunction "NC_28") (pintype "input+no_connect"))
    )
    (net (code "124") (name "unconnected-(U3-SYNC_IN-Pad13)") (class "Default")
      (node (ref "U3") (pin "13") (pinfunction "SYNC_IN_13") (pintype "input+no_connect"))
    )
    (net (code "125") (name "unconnected-(USBC1-SBU1-PadA8)") (class "Default")
      (node (ref "USBC1") (pin "A8") (pinfunction "SBU1_A8") (pintype "input+no_connect"))
    )
    (net (code "126") (name "unconnected-(USBC1-SBU2-PadB8)") (class "Default")
      (node (ref "USBC1") (pin "B8") (pinfunction "SBU2_B8") (pintype "input+no_connect"))
    )
  )
)
